# Power.net
KiCad netlist of a schematic drawn in Altium Designer
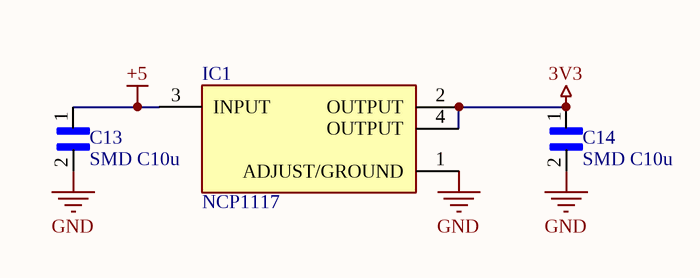
[diagram p0: Power.SchDoc]

(export (version "E")
  (design (tool "Eeschema 10.0.6"))
  (components
    (comp (ref "C13")
      (value "SMD C10u")
      (footprint "SMD Capacetor-Footprint-1")
      (description "Generic SMD Capacetor")
      (libsource (lib "Tobias") (part "10u"))
    )
    (comp (ref "C14")
      (value "SMD C10u")
      (footprint "SMD Capacetor-Footprint-1")
      (description "Generic SMD Capacetor")
      (libsource (lib "Tobias") (part "10u"))
    )
    (comp (ref "IC1")
      (value "NCP1117")
      (footprint "NCP1117-Footprint-1")
      (description "Voltage Stabalizer")
      (libsource (lib "Tobias") (part "NCP1117-Symbol-1"))
    )
  )
  (nets
    (net (code "1") (name "+5") (class "Default")
      (node (ref "C13") (pin "1") (pinfunction "1_1") (pintype "passive"))
      (node (ref "IC1") (pin "3") (pinfunction "INPUT_3") (pintype "power_in"))
    )
    (net (code "2") (name "3V3") (class "Default")
      (node (ref "C14") (pin "1") (pinfunction "1_1") (pintype "passive"))
      (node (ref "IC1") (pin "2") (pinfunction "OUTPUT_2") (pintype "power_in"))
      (node (ref "IC1") (pin "4") (pinfunction "OUTPUT_4") (pintype "power_in"))
    )
    (net (code "3") (name "GND") (class "Default")
      (node (ref "C13") (pin "2") (pinfunction "2_2") (pintype "passive"))
      (node (ref "C14") (pin "2") (pinfunction "2_2") (pintype "passive"))
      (node (ref "IC1") (pin "1") (pinfunction "ADJUST/GROUND_1") (pintype "passive"))
    )
  )
)
